# Sheet2_Power_Supply.net
KiCad netlist of a schematic drawn in Altium Designer
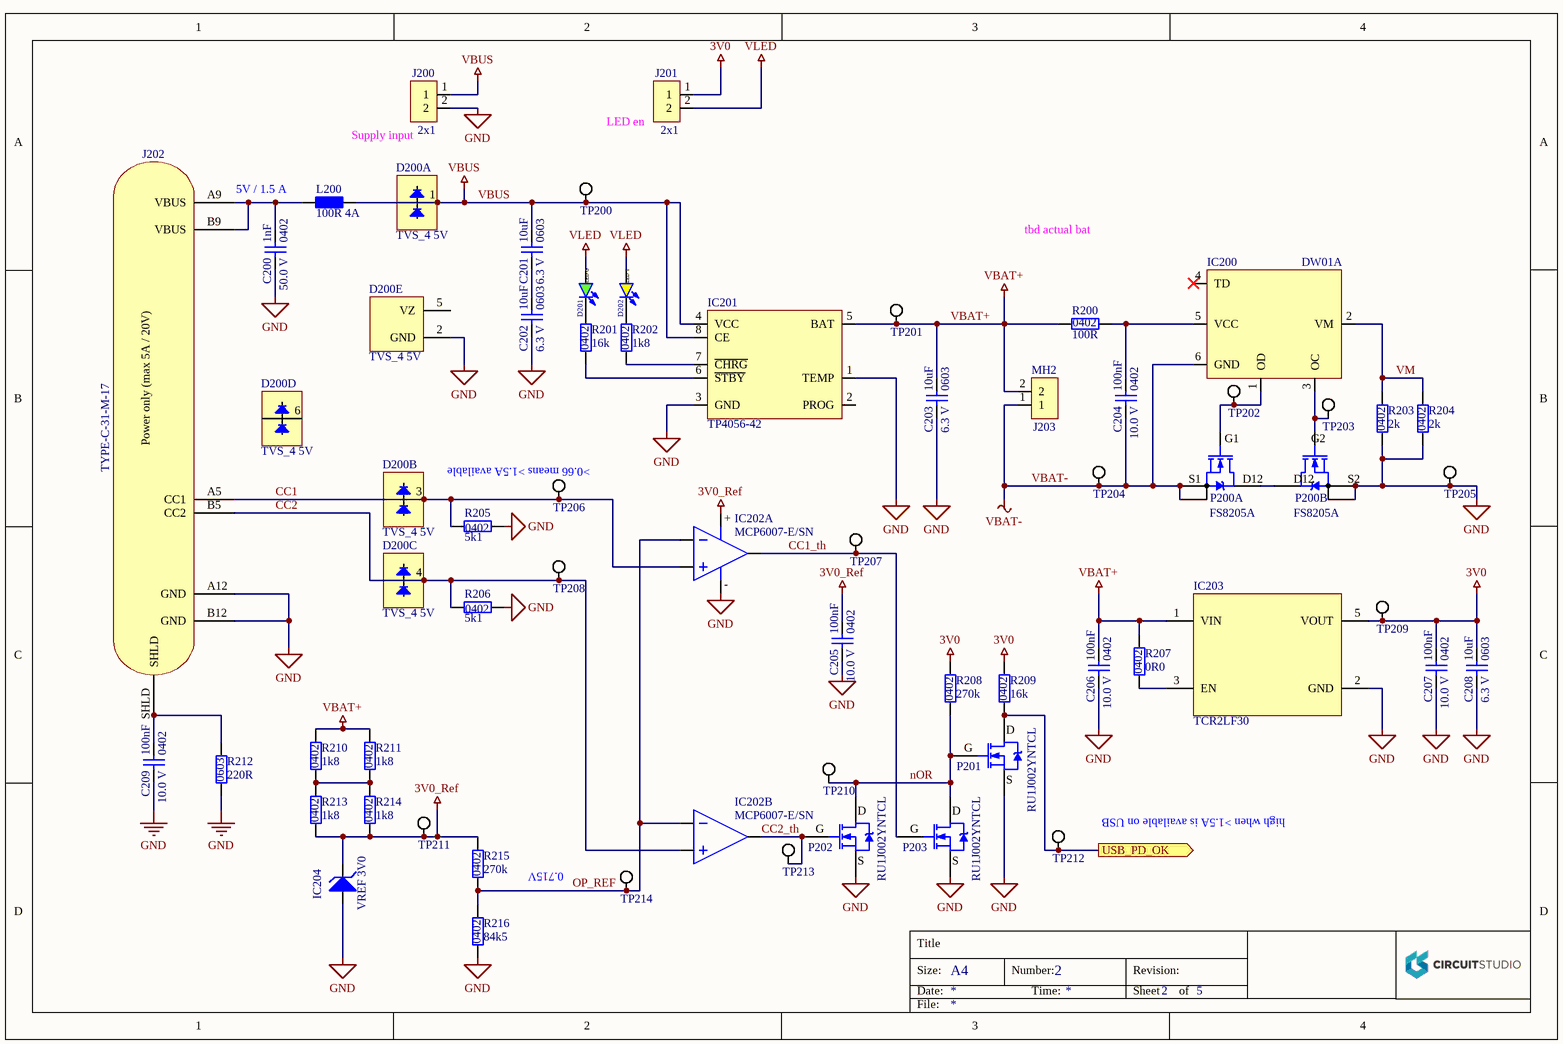
[diagram p0: Sheet2_Power_Supply.SchDoc]

(export (version "E")
  (design (tool "Eeschema 10.0.6"))
  (components
    (comp (ref "C200")
      (value "C 1nF 0402 50V")
      (footprint "0402")
      (description "CAP CER 1000PF 50V C0G/NP0 0402")
      (fields
        (field (name "MANUFACTURER") "Murata Electronics")
        (field (name "MANUFACTURER PART NUMBER") "GRM1555C1H102JA01J")
        (field (name "CAPACITANCE") "1nF")
        (field (name "VOLTAGE") "50.0 V")
      )
      (libsource (lib "CS_Part_Library") (part "CAP_1nF_50V_0402"))
    )
    (comp (ref "C201")
      (value "C 10uF 0603 6.3V")
      (footprint "0603")
      (description "CAP CER 10UF 6.3V X5R 0603")
      (fields
        (field (name "MANUFACTURER") "Taiyo Yuden")
        (field (name "MANUFACTURER PART NUMBER") "JMK107ABJ106MA-T")
        (field (name "CAPACITANCE") "10uF")
        (field (name "VOLTAGE") "6.3 V")
      )
      (libsource (lib "CS_Part_Library") (part "CAP_10uF_6V3_0603"))
    )
    (comp (ref "C202")
      (value "C 10uF 0603 6.3V")
      (footprint "0603")
      (description "CAP CER 10UF 6.3V X5R 0603")
      (fields
        (field (name "MANUFACTURER") "Taiyo Yuden")
        (field (name "MANUFACTURER PART NUMBER") "JMK107ABJ106MA-T")
        (field (name "CAPACITANCE") "10uF")
        (field (name "VOLTAGE") "6.3 V")
      )
      (libsource (lib "CS_Part_Library") (part "CAP_10uF_6V3_0603"))
    )
    (comp (ref "C203")
      (value "C 10uF 0603 6.3V")
      (footprint "0603")
      (description "CAP CER 10UF 6.3V X5R 0603")
      (fields
        (field (name "MANUFACTURER") "Taiyo Yuden")
        (field (name "MANUFACTURER PART NUMBER") "JMK107ABJ106MA-T")
        (field (name "CAPACITANCE") "10uF")
        (field (name "VOLTAGE") "6.3 V")
      )
      (libsource (lib "CS_Part_Library") (part "CAP_10uF_6V3_0603"))
    )
    (comp (ref "C204")
      (value "C 100nF 0402 10V")
      (footprint "0402")
      (description "CAP CER 0.1UF 10V X5R 0402")
      (fields
        (field (name "MANUFACTURER") "Samsung Electro-Mechanics")
        (field (name "MANUFACTURER PART NUMBER") "CL05A104MP5NNNC")
        (field (name "CAPACITANCE") "100nF")
        (field (name "VOLTAGE") "10.0 V")
      )
      (libsource (lib "CS_Part_Library") (part "CAP_100nF_10V_0402"))
    )
    (comp (ref "C205")
      (value "C 100nF 0402 10V")
      (footprint "0402")
      (description "CAP CER 0.1UF 10V X5R 0402")
      (fields
        (field (name "MANUFACTURER") "Samsung Electro-Mechanics")
        (field (name "MANUFACTURER PART NUMBER") "CL05A104MP5NNNC")
        (field (name "CAPACITANCE") "100nF")
        (field (name "VOLTAGE") "10.0 V")
      )
      (libsource (lib "CS_Part_Library") (part "CAP_100nF_10V_0402"))
    )
    (comp (ref "C206")
      (value "C 100nF 0402 10V")
      (footprint "0402")
      (description "CAP CER 0.1UF 10V X5R 0402")
      (fields
        (field (name "MANUFACTURER") "Samsung Electro-Mechanics")
        (field (name "MANUFACTURER PART NUMBER") "CL05A104MP5NNNC")
        (field (name "CAPACITANCE") "100nF")
        (field (name "VOLTAGE") "10.0 V")
      )
      (libsource (lib "CS_Part_Library") (part "CAP_100nF_10V_0402"))
    )
    (comp (ref "C207")
      (value "C 100nF 0402 10V")
      (footprint "0402")
      (description "CAP CER 0.1UF 10V X5R 0402")
      (fields
        (field (name "MANUFACTURER") "Samsung Electro-Mechanics")
        (field (name "MANUFACTURER PART NUMBER") "CL05A104MP5NNNC")
        (field (name "CAPACITANCE") "100nF")
        (field (name "VOLTAGE") "10.0 V")
      )
      (libsource (lib "CS_Part_Library") (part "CAP_100nF_10V_0402"))
    )
    (comp (ref "C208")
      (value "C 10uF 0603 6.3V")
      (footprint "0603")
      (description "CAP CER 10UF 6.3V X5R 0603")
      (fields
        (field (name "MANUFACTURER") "Taiyo Yuden")
        (field (name "MANUFACTURER PART NUMBER") "JMK107ABJ106MA-T")
        (field (name "CAPACITANCE") "10uF")
        (field (name "VOLTAGE") "6.3 V")
      )
      (libsource (lib "CS_Part_Library") (part "CAP_10uF_6V3_0603"))
    )
    (comp (ref "C209")
      (value "C 100nF 0402 10V")
      (footprint "0402")
      (description "CAP CER 0.1UF 10V X5R 0402")
      (fields
        (field (name "MANUFACTURER") "Samsung Electro-Mechanics")
        (field (name "MANUFACTURER PART NUMBER") "CL05A104MP5NNNC")
        (field (name "CAPACITANCE") "100nF")
        (field (name "VOLTAGE") "10.0 V")
      )
      (libsource (lib "CS_Part_Library") (part "CAP_100nF_10V_0402"))
    )
    (comp (ref "D200")
      (value "TVS_4 5V")
      (footprint "SOT-23-6")
      (description "TVS DIODE 5VWM 12.5VC SOT23-6")
      (fields
        (field (name "MANUFACTURER") "Comchip Technology")
        (field (name "MANUFACTURER PART NUMBER") "CPDT6-5V0UPC-HF")
      )
      (libsource (lib "CS_Part_Library") (part "D_TVS_U4_12V5"))
    )
    (comp (ref "D201")
      (value "LED G")
      (footprint "LED_0603")
      (description "LED GREEN DIFFUSED 0603 SMD")
      (fields
        (field (name "MANUFACTURER") "OSRAM Opto Semiconductors Inc.")
        (field (name "MANUFACTURER PART NUMBER") "LT Q39G-Q1OO-25-1")
      )
      (libsource (lib "CS_Part_Library") (part "D_LED_Green_0603"))
    )
    (comp (ref "D202")
      (value "LED Y")
      (footprint "LED_0603")
      (description "LED YELLOW DIFFUSED")
      (fields
        (field (name "MANUFACTURER") "Stanley Electric Co")
        (field (name "MANUFACTURER PART NUMBER") "FKY1111C-TR")
      )
      (libsource (lib "CS_Part_Library") (part "D_LED_Yellow_0603"))
    )
    (comp (ref "IC200")
      (value "DW01A")
      (footprint "SOT-23-6")
      (description "IC BATT MANAGEMENT SOT-23-6")
      (fields (field (name "MANUFACTURER") "PUOLOP"))
      (libsource (lib "CS_Part_Library") (part "IC_BAT_PROT_DW01A"))
    )
    (comp (ref "IC201")
      (value "TP4056-42")
      (footprint "SOIC-8-EP")
      (description "IC BATT CHG LI-ION 1CELL ESOP-8-EP")
      (fields
        (field (name "MANUFACTURER") "TOPPOWER(Nanjing Extension Microelectronics)")
        (field (name "MANUFACTURER PART NUMBER") "TP4056-42-ESOP8")
      )
      (libsource (lib "Symbols") (part "IC_BAT_CHGR_TP4056"))
    )
    (comp (ref "IC202")
      (value "MCP6007-E/SN")
      (footprint "SOIC-8")
      (description "DUAL, 1MHZ OP AMP, E TEMP")
      (fields (field (name "MANUFACTURER") "Microchip Technology"))
      (libsource (lib "CS_Part_Library") (part "IC_OpAmp_MCP6007-E/SN"))
    )
    (comp (ref "IC203")
      (value "TCR2LF30")
      (footprint "SOT-23-5")
      (description "IC REG LINEAR 3V 200MA SMV")
      (fields
        (field (name "MANUFACTURER") "Toshiba Semiconductor and Storage")
        (field (name "MANUFACTURER PART NUMBER") "TCR2LF30,LM(CT")
      )
      (libsource (lib "CS_Part_Library") (part "IC_Reg_TCR2LF30"))
    )
    (comp (ref "IC204")
      (value "VREF 3V0")
      (footprint "SOT-23-3")
      (description "IC VREF SHUNT 1% SOT23-3")
      (fields
        (field (name "MANUFACTURER") "Texas Instruments")
        (field (name "MANUFACTURER PART NUMBER") "LM4040DIM3X-3.0/NOPB")
      )
      (libsource (lib "Symbols") (part "IC_Ref_LM4040DIM3X-3.0"))
    )
    (comp (ref "J200")
      (value "2x1")
      (footprint "PH_1x2")
      (description "CONN HEADER VERT 2POS 2.54MM")
      (fields
        (field (name "MANUFACTURER") "Sullins Connector Solutions")
        (field (name "MANUFACTURER PART NUMBER") "PRPC002SAAN-RC")
      )
      (libsource (lib "CS_Part_Library") (part "J_MH2x1_2.54"))
    )
    (comp (ref "J201")
      (value "2x1")
      (footprint "PH_1x2")
      (description "CONN HEADER VERT 2POS 2.54MM")
      (fields
        (field (name "MANUFACTURER") "Sullins Connector Solutions")
        (field (name "MANUFACTURER PART NUMBER") "PRPC002SAAN-RC")
      )
      (libsource (lib "CS_Part_Library") (part "J_MH2x1_2.54"))
    )
    (comp (ref "J202")
      (value "TYPE-C-31-M-17")
      (footprint "Con_TYPE-C-31-M-17")
      (description "USB4 GEN3, TYPE C, TOP MOUNT")
      (fields (field (name "MANUFACTURER") "Korean Hroparts Elec"))
      (libsource (lib "CS_Part_Library") (part "J_USB-C_2"))
    )
    (comp (ref "J203")
      (value "MH2")
      (footprint "J_S2B-PH-K-S")
      (description "CONN HEADER R/A 2POS 2MM")
      (fields
        (field (name "MANUFACTURER") "JST Sales America Inc.")
        (field (name "MANUFACTURER PART NUMBER") "S2B-PH-KL(LF)(SN)")
      )
      (libsource (lib "CS_Part_Library") (part "J_S2B-PH-KL"))
    )
    (comp (ref "L200")
      (value "L Ferrite 100R 4A")
      (footprint "L_1206")
      (description "FIXED IND 100 4000MA 1206")
      (fields
        (field (name "MANUFACTURER") "Eaton - Electronics Division")
        (field (name "MANUFACTURER PART NUMBER") "MFBM1V3216-101-R")
        (field (name "INDUCTANCE") "100R 4A")
      )
      (libsource (lib "CS_Part_Library") (part "L_100R_4A"))
    )
    (comp (ref "P200")
      (value "P2 NMOS 20V 6A")
      (footprint "TSSOP-8_4.4mm")
      (description "MOSFET 2N_CH 20V 6A TSSOP-8")
      (fields
        (field (name "MANUFACTURER") "Fortune Semicon")
        (field (name "MANUFACTURER PART NUMBER") "FS8205A")
      )
      (libsource (lib "CS_Part_Library") (part "P_2NCH_20V_1W"))
    )
    (comp (ref "P201")
      (value "P_NCH_50V_150mW")
      (footprint "UMT3F")
      (description "MOSFET N-CH 50V 200MA UMT3F")
      (fields
        (field (name "MANUFACTURER") "Rohm Semiconductor")
        (field (name "MANUFACTURER PART NUMBER") "RU1J002YNTCL")
      )
      (libsource (lib "CS_Part_Library") (part "P_NCH_50V_150mW"))
    )
    (comp (ref "P202")
      (value "P_NCH_50V_150mW")
      (footprint "UMT3F")
      (description "MOSFET N-CH 50V 200MA UMT3F")
      (fields
        (field (name "MANUFACTURER") "Rohm Semiconductor")
        (field (name "MANUFACTURER PART NUMBER") "RU1J002YNTCL")
      )
      (libsource (lib "CS_Part_Library") (part "P_NCH_50V_150mW"))
    )
    (comp (ref "P203")
      (value "P_NCH_50V_150mW")
      (footprint "UMT3F")
      (description "MOSFET N-CH 50V 200MA UMT3F")
      (fields
        (field (name "MANUFACTURER") "Rohm Semiconductor")
        (field (name "MANUFACTURER PART NUMBER") "RU1J002YNTCL")
      )
      (libsource (lib "CS_Part_Library") (part "P_NCH_50V_150mW"))
    )
    (comp (ref "R200")
      (value "R 100R 0402")
      (footprint "0402")
      (description "RES 100 OHM 1% 1/16W 0402")
      (fields
        (field (name "MANUFACTURER") "Stackpole Electronics Inc")
        (field (name "MANUFACTURER PART NUMBER") "RMCF0402FT100R")
        (field (name "RESISTANCE") "100R")
      )
      (libsource (lib "CS_Part_Library") (part "R_100R_0402"))
    )
    (comp (ref "R201")
      (value "R 16k 0402")
      (footprint "0402")
      (description "RES 16K OHM 1% 1/16W 0402")
      (fields
        (field (name "MANUFACTURER") "Stackpole Electronics Inc")
        (field (name "MANUFACTURER PART NUMBER") "RMCF0402FT16K0")
        (field (name "RESISTANCE") "16k")
      )
      (libsource (lib "CS_Part_Library") (part "R_16k_0402"))
    )
    (comp (ref "R202")
      (value "R 1k8 0402")
      (footprint "0402")
      (description "RES 1.8K OHM 1% 1/16W 0402")
      (fields
        (field (name "MANUFACTURER") "Stackpole Electronics Inc")
        (field (name "MANUFACTURER PART NUMBER") "RMCF0402FT1K80")
        (field (name "RESISTANCE") "1k8")
      )
      (libsource (lib "CS_Part_Library") (part "R_1k8_0402"))
    )
    (comp (ref "R203")
      (value "R 2k 0402")
      (footprint "0402")
      (description "RES 2K OHM 1% 1/16W 0402")
      (fields
        (field (name "MANUFACTURER") "Stackpole Electronics Inc")
        (field (name "MANUFACTURER PART NUMBER") "RMCF0402FT2K00")
        (field (name "RESISTANCE") "2k")
      )
      (libsource (lib "CS_Part_Library") (part "R_2k_0402"))
    )
    (comp (ref "R204")
      (value "R 2k 0402")
      (footprint "0402")
      (description "RES 2K OHM 1% 1/16W 0402")
      (fields
        (field (name "MANUFACTURER") "Stackpole Electronics Inc")
        (field (name "MANUFACTURER PART NUMBER") "RMCF0402FT2K00")
        (field (name "RESISTANCE") "2k")
      )
      (libsource (lib "CS_Part_Library") (part "R_2k_0402"))
    )
    (comp (ref "R205")
      (value "R 5k1 0402")
      (footprint "0402")
      (description "RES 5.1K OHM 1% 1/16W 0402")
      (fields
        (field (name "MANUFACTURER") "Stackpole Electronics Inc")
        (field (name "MANUFACTURER PART NUMBER") "RMCF0402FT5K10")
        (field (name "RESISTANCE") "5k1")
      )
      (libsource (lib "CS_Part_Library") (part "R_5k1_0420"))
    )
    (comp (ref "R206")
      (value "R 5k1 0402")
      (footprint "0402")
      (description "RES 5.1K OHM 1% 1/16W 0402")
      (fields
        (field (name "MANUFACTURER") "Stackpole Electronics Inc")
        (field (name "MANUFACTURER PART NUMBER") "RMCF0402FT5K10")
        (field (name "RESISTANCE") "5k1")
      )
      (libsource (lib "CS_Part_Library") (part "R_5k1_0420"))
    )
    (comp (ref "R207")
      (value "R 0R0 0402")
      (footprint "0402")
      (description "RES 0 OHM JUMPER 1/16W 0402")
      (fields
        (field (name "MANUFACTURER") "Stackpole Electronics Inc")
        (field (name "MANUFACTURER PART NUMBER") "RMCF0402ZT0R00")
        (field (name "RESISTANCE") "0R0")
      )
      (libsource (lib "CS_Part_Library") (part "R_0R0_0402"))
    )
    (comp (ref "R208")
      (value "R 270k 0402")
      (footprint "0402")
      (description "RES 270K OHM 1% 1/16W 0402")
      (fields
        (field (name "MANUFACTURER") "YAGEO")
        (field (name "MANUFACTURER PART NUMBER") "RC0402FR-07270KL")
        (field (name "RESISTANCE") "270k")
      )
      (libsource (lib "CS_Part_Library") (part "R_270k_0402"))
    )
    (comp (ref "R209")
      (value "R 16k 0402")
      (footprint "0402")
      (description "RES 16K OHM 1% 1/16W 0402")
      (fields
        (field (name "MANUFACTURER") "Stackpole Electronics Inc")
        (field (name "MANUFACTURER PART NUMBER") "RMCF0402FT16K0")
        (field (name "RESISTANCE") "16k")
      )
      (libsource (lib "CS_Part_Library") (part "R_16k_0402"))
    )
    (comp (ref "R210")
      (value "R 1k8 0402")
      (footprint "0402")
      (description "RES 1.8K OHM 1% 1/16W 0402")
      (fields
        (field (name "MANUFACTURER") "Stackpole Electronics Inc")
        (field (name "MANUFACTURER PART NUMBER") "RMCF0402FT1K80")
        (field (name "RESISTANCE") "1k8")
      )
      (libsource (lib "CS_Part_Library") (part "R_1k8_0402"))
    )
    (comp (ref "R211")
      (value "R 1k8 0402")
      (footprint "0402")
      (description "RES 1.8K OHM 1% 1/16W 0402")
      (fields
        (field (name "MANUFACTURER") "Stackpole Electronics Inc")
        (field (name "MANUFACTURER PART NUMBER") "RMCF0402FT1K80")
        (field (name "RESISTANCE") "1k8")
      )
      (libsource (lib "CS_Part_Library") (part "R_1k8_0402"))
    )
    (comp (ref "R212")
      (value "R 220R 0603")
      (footprint "0603")
      (description "RES 220 OHM 1% 1/10W 0603")
      (fields
        (field (name "MANUFACTURER") "Stackpole Electronics Inc")
        (field (name "MANUFACTURER PART NUMBER") "RMCF0603FT220R")
        (field (name "RESISTANCE") "220R")
      )
      (libsource (lib "CS_Part_Library") (part "R_220R_0603"))
    )
    (comp (ref "R213")
      (value "R 1k8 0402")
      (footprint "0402")
      (description "RES 1.8K OHM 1% 1/16W 0402")
      (fields
        (field (name "MANUFACTURER") "Stackpole Electronics Inc")
        (field (name "MANUFACTURER PART NUMBER") "RMCF0402FT1K80")
        (field (name "RESISTANCE") "1k8")
      )
      (libsource (lib "CS_Part_Library") (part "R_1k8_0402"))
    )
    (comp (ref "R214")
      (value "R 1k8 0402")
      (footprint "0402")
      (description "RES 1.8K OHM 1% 1/16W 0402")
      (fields
        (field (name "MANUFACTURER") "Stackpole Electronics Inc")
        (field (name "MANUFACTURER PART NUMBER") "RMCF0402FT1K80")
        (field (name "RESISTANCE") "1k8")
      )
      (libsource (lib "CS_Part_Library") (part "R_1k8_0402"))
    )
    (comp (ref "R215")
      (value "R 270k 0402")
      (footprint "0402")
      (description "RES 270K OHM 1% 1/16W 0402")
      (fields
        (field (name "MANUFACTURER") "YAGEO")
        (field (name "MANUFACTURER PART NUMBER") "RC0402FR-07270KL")
        (field (name "RESISTANCE") "270k")
      )
      (libsource (lib "CS_Part_Library") (part "R_270k_0402"))
    )
    (comp (ref "R216")
      (value "R 84k5 0402")
      (footprint "0402")
      (description "RES SMD 84.5K OHM 1% 1/16W 0402")
      (fields
        (field (name "MANUFACTURER") "Vishay Dale")
        (field (name "MANUFACTURER PART NUMBER") "CRCW040284K5FKED")
        (field (name "RESISTANCE") "84k5")
      )
      (libsource (lib "CS_Part_Library") (part "R_84k5_0402"))
    )
    (comp (ref "TP200")
      (value "TP")
      (footprint "TP_1mm")
      (description "Test Point 1mm")
      (libsource (lib "CS_Part_Library") (part "TP_1mm"))
    )
    (comp (ref "TP201")
      (value "TP")
      (footprint "TP_1mm")
      (description "Test Point 1mm")
      (libsource (lib "CS_Part_Library") (part "TP_1mm"))
    )
    (comp (ref "TP202")
      (value "TP")
      (footprint "TP_1mm")
      (description "Test Point 1mm")
      (libsource (lib "CS_Part_Library") (part "TP_1mm"))
    )
    (comp (ref "TP203")
      (value "TP")
      (footprint "TP_1mm")
      (description "Test Point 1mm")
      (libsource (lib "CS_Part_Library") (part "TP_1mm"))
    )
    (comp (ref "TP204")
      (value "TP")
      (footprint "TP_1mm")
      (description "Test Point 1mm")
      (libsource (lib "CS_Part_Library") (part "TP_1mm"))
    )
    (comp (ref "TP205")
      (value "TP")
      (footprint "TP_1mm")
      (description "Test Point 1mm")
      (libsource (lib "CS_Part_Library") (part "TP_1mm"))
    )
    (comp (ref "TP206")
      (value "TP")
      (footprint "TP_1mm")
      (description "Test Point 1mm")
      (libsource (lib "CS_Part_Library") (part "TP_1mm"))
    )
    (comp (ref "TP207")
      (value "TP")
      (footprint "TP_1mm")
      (description "Test Point 1mm")
      (libsource (lib "CS_Part_Library") (part "TP_1mm"))
    )
    (comp (ref "TP208")
      (value "TP")
      (footprint "TP_1mm")
      (description "Test Point 1mm")
      (libsource (lib "CS_Part_Library") (part "TP_1mm"))
    )
    (comp (ref "TP209")
      (value "TP")
      (footprint "TP_1mm")
      (description "Test Point 1mm")
      (libsource (lib "CS_Part_Library") (part "TP_1mm"))
    )
    (comp (ref "TP210")
      (value "TP")
      (footprint "TP_1mm")
      (description "Test Point 1mm")
      (libsource (lib "CS_Part_Library") (part "TP_1mm"))
    )
    (comp (ref "TP211")
      (value "TP")
      (footprint "TP_1mm")
      (description "Test Point 1mm")
      (libsource (lib "CS_Part_Library") (part "TP_1mm"))
    )
    (comp (ref "TP212")
      (value "TP")
      (footprint "TP_1mm")
      (description "Test Point 1mm")
      (libsource (lib "CS_Part_Library") (part "TP_1mm"))
    )
    (comp (ref "TP213")
      (value "TP")
      (footprint "TP_1mm")
      (description "Test Point 1mm")
      (libsource (lib "CS_Part_Library") (part "TP_1mm"))
    )
    (comp (ref "TP214")
      (value "TP")
      (footprint "TP_1mm")
      (description "Test Point 1mm")
      (libsource (lib "CS_Part_Library") (part "TP_1mm"))
    )
  )
  (nets
    (net (code "1") (name "/CC1") (class "Default")
      (node (ref "D200") (pin "3") (pinfunction "3_3") (pintype "passive"))
      (node (ref "IC202") (pin "3") (pinfunction "INA+_3") (pintype "passive"))
      (node (ref "J202") (pin "A5") (pinfunction "CC1_A5") (pintype "passive"))
      (node (ref "R205") (pin "2") (pinfunction "2_2") (pintype "passive"))
      (node (ref "TP206") (pin "1") (pinfunction "TP_1") (pintype "passive"))
    )
    (net (code "2") (name "/CC1_th") (class "Default")
      (node (ref "IC202") (pin "1") (pinfunction "OUTA_1") (pintype "passive"))
      (node (ref "P203") (pin "1") (pinfunction "G_1") (pintype "passive"))
      (node (ref "TP207") (pin "1") (pinfunction "TP_1") (pintype "passive"))
    )
    (net (code "3") (name "/CC2") (class "Default")
      (node (ref "D200") (pin "4") (pinfunction "4_4") (pintype "passive"))
      (node (ref "IC202") (pin "5") (pinfunction "INB+_5") (pintype "passive"))
      (node (ref "J202") (pin "B5") (pinfunction "CC2_B5") (pintype "passive"))
      (node (ref "R206") (pin "2") (pinfunction "2_2") (pintype "passive"))
      (node (ref "TP208") (pin "1") (pinfunction "TP_1") (pintype "passive"))
    )
    (net (code "4") (name "/CC2_th") (class "Default")
      (node (ref "IC202") (pin "7") (pinfunction "OUTB_7") (pintype "passive"))
      (node (ref "P202") (pin "1") (pinfunction "G_1") (pintype "passive"))
      (node (ref "TP213") (pin "1") (pinfunction "TP_1") (pintype "passive"))
    )
    (net (code "5") (name "/OP_REF") (class "Default")
      (node (ref "IC202") (pin "2") (pinfunction "INA-_2") (pintype "passive"))
      (node (ref "IC202") (pin "6") (pinfunction "INB-_6") (pintype "passive"))
      (node (ref "R215") (pin "1") (pinfunction "1_1") (pintype "passive"))
      (node (ref "R216") (pin "2") (pinfunction "2_2") (pintype "passive"))
      (node (ref "TP214") (pin "1") (pinfunction "TP_1") (pintype "passive"))
    )
    (net (code "6") (name "/USB_PD_OK") (class "Default")
      (node (ref "P201") (pin "3") (pinfunction "D_3") (pintype "passive"))
      (node (ref "R209") (pin "1") (pinfunction "1_1") (pintype "passive"))
      (node (ref "TP212") (pin "1") (pinfunction "TP_1") (pintype "passive"))
    )
    (net (code "7") (name "/VM") (class "Default")
      (node (ref "IC200") (pin "2") (pinfunction "VM_2") (pintype "passive"))
      (node (ref "R203") (pin "2") (pinfunction "2_2") (pintype "passive"))
      (node (ref "R204") (pin "2") (pinfunction "2_2") (pintype "passive"))
    )
    (net (code "8") (name "/nOR") (class "Default")
      (node (ref "P201") (pin "1") (pinfunction "G_1") (pintype "passive"))
      (node (ref "P202") (pin "3") (pinfunction "D_3") (pintype "passive"))
      (node (ref "P203") (pin "3") (pinfunction "D_3") (pintype "passive"))
      (node (ref "R208") (pin "1") (pinfunction "1_1") (pintype "passive"))
      (node (ref "TP210") (pin "1") (pinfunction "TP_1") (pintype "passive"))
    )
    (net (code "9") (name "3V0") (class "Default")
      (node (ref "C207") (pin "2") (pinfunction "2_2") (pintype "passive"))
      (node (ref "C208") (pin "2") (pinfunction "2_2") (pintype "passive"))
      (node (ref "IC203") (pin "5") (pinfunction "VOUT_5") (pintype "passive"))
      (node (ref "J201") (pin "1") (pinfunction "1_1") (pintype "passive"))
      (node (ref "R208") (pin "2") (pinfunction "2_2") (pintype "passive"))
      (node (ref "R209") (pin "2") (pinfunction "2_2") (pintype "passive"))
      (node (ref "TP209") (pin "1") (pinfunction "TP_1") (pintype "passive"))
    )
    (net (code "10") (name "3V0_Ref") (class "Default")
      (node (ref "C205") (pin "2") (pinfunction "2_2") (pintype "passive"))
      (node (ref "IC202") (pin "8") (pinfunction "VDD_8") (pintype "passive"))
      (node (ref "IC204") (pin "1") (pinfunction "K_1") (pintype "passive"))
      (node (ref "R213") (pin "1") (pinfunction "1_1") (pintype "passive"))
      (node (ref "R214") (pin "1") (pinfunction "1_1") (pintype "passive"))
      (node (ref "R215") (pin "2") (pinfunction "2_2") (pintype "passive"))
      (node (ref "TP211") (pin "1") (pinfunction "TP_1") (pintype "passive"))
    )
    (net (code "11") (name "GND") (class "Default")
      (node (ref "C200") (pin "1") (pinfunction "1_1") (pintype "passive"))
      (node (ref "C202") (pin "1") (pinfunction "1_1") (pintype "passive"))
      (node (ref "C203") (pin "1") (pinfunction "1_1") (pintype "passive"))
      (node (ref "C205") (pin "1") (pinfunction "1_1") (pintype "passive"))
      (node (ref "C206") (pin "1") (pinfunction "1_1") (pintype "passive"))
      (node (ref "C207") (pin "1") (pinfunction "1_1") (pintype "passive"))
      (node (ref "C208") (pin "1") (pinfunction "1_1") (pintype "passive"))
      (node (ref "C209") (pin "1") (pinfunction "1_1") (pintype "passive"))
      (node (ref "D200") (pin "2") (pinfunction "GND_2") (pintype "passive"))
      (node (ref "IC201") (pin "1") (pinfunction "TEMP_1") (pintype "passive"))
      (node (ref "IC201") (pin "3") (pinfunction "GND_3") (pintype "passive"))
      (node (ref "IC202") (pin "4") (pinfunction "VSS_4") (pintype "passive"))
      (node (ref "IC203") (pin "2") (pinfunction "GND_2") (pintype "passive"))
      (node (ref "IC204") (pin "2") (pinfunction "A_2") (pintype "passive"))
      (node (ref "J200") (pin "2") (pinfunction "2_2") (pintype "passive"))
      (node (ref "J202") (pin "A12") (pinfunction "GND_A12") (pintype "passive"))
      (node (ref "J202") (pin "B12") (pinfunction "GND_B12") (pintype "passive"))
      (node (ref "P200") (pin "6") (pinfunction "S2_6") (pintype "passive"))
      (node (ref "P200") (pin "7") (pinfunction "S2_7") (pintype "passive"))
      (node (ref "P201") (pin "2") (pinfunction "S_2") (pintype "passive"))
      (node (ref "P202") (pin "2") (pinfunction "S_2") (pintype "passive"))
      (node (ref "P203") (pin "2") (pinfunction "S_2") (pintype "passive"))
      (node (ref "R203") (pin "1") (pinfunction "1_1") (pintype "passive"))
      (node (ref "R204") (pin "1") (pinfunction "1_1") (pintype "passive"))
      (node (ref "R205") (pin "1") (pinfunction "1_1") (pintype "passive"))
      (node (ref "R206") (pin "1") (pinfunction "1_1") (pintype "passive"))
      (node (ref "R212") (pin "1") (pinfunction "1_1") (pintype "passive"))
      (node (ref "R216") (pin "1") (pinfunction "1_1") (pintype "passive"))
      (node (ref "TP205") (pin "1") (pinfunction "TP_1") (pintype "passive"))
    )
    (net (code "12") (name "Net-(C200-Pad2)") (class "Default")
      (node (ref "C200") (pin "2") (pinfunction "2_2") (pintype "passive"))
      (node (ref "J202") (pin "A9") (pinfunction "VBUS_A9") (pintype "passive"))
      (node (ref "J202") (pin "B9") (pinfunction "VBUS_B9") (pintype "passive"))
      (node (ref "L200") (pin "1") (pinfunction "1_1") (pintype "passive"))
    )
    (net (code "13") (name "Net-(C201-Pad1)") (class "Default")
      (node (ref "C201") (pin "1") (pinfunction "1_1") (pintype "passive"))
      (node (ref "C202") (pin "2") (pinfunction "2_2") (pintype "passive"))
    )
    (net (code "14") (name "Net-(C209-Pad2)") (class "Default")
      (node (ref "C209") (pin "2") (pinfunction "2_2") (pintype "passive"))
      (node (ref "J202") (pin "SHLD") (pinfunction "SHLD_SHLD") (pintype "passive"))
      (node (ref "R212") (pin "2") (pinfunction "2_2") (pintype "passive"))
    )
    (net (code "15") (name "Net-(D201-PadK)") (class "Default")
      (node (ref "D201") (pin "K") (pinfunction "K_K") (pintype "passive"))
      (node (ref "R201") (pin "2") (pinfunction "2_2") (pintype "passive"))
    )
    (net (code "16") (name "Net-(D202-PadK)") (class "Default")
      (node (ref "D202") (pin "K") (pinfunction "K_K") (pintype "passive"))
      (node (ref "R202") (pin "2") (pinfunction "2_2") (pintype "passive"))
    )
    (net (code "17") (name "Net-(IC200-OC)") (class "Default")
      (node (ref "IC200") (pin "3") (pinfunction "OC_3") (pintype "passive"))
      (node (ref "P200") (pin "5") (pinfunction "G1_5") (pintype "passive"))
      (node (ref "TP203") (pin "1") (pinfunction "TP_1") (pintype "passive"))
    )
    (net (code "18") (name "Net-(IC200-OD)") (class "Default")
      (node (ref "IC200") (pin "1") (pinfunction "OD_1") (pintype "passive"))
      (node (ref "P200") (pin "4") (pinfunction "G1_4") (pintype "passive"))
      (node (ref "TP202") (pin "1") (pinfunction "TP_1") (pintype "passive"))
    )
    (net (code "19") (name "Net-(IC200-VCC)") (class "Default")
      (node (ref "C204") (pin "2") (pinfunction "2_2") (pintype "passive"))
      (node (ref "IC200") (pin "5") (pinfunction "VCC_5") (pintype "passive"))
      (node (ref "R200") (pin "2") (pinfunction "2_2") (pintype "passive"))
    )
    (net (code "20") (name "Net-(IC201-~{CHRG})") (class "Default")
      (node (ref "IC201") (pin "7") (pinfunction "~{CHRG}_7") (pintype "passive"))
      (node (ref "R202") (pin "1") (pinfunction "1_1") (pintype "passive"))
    )
    (net (code "21") (name "Net-(IC201-~{STBY})") (class "Default")
      (node (ref "IC201") (pin "6") (pinfunction "~{STBY}_6") (pintype "passive"))
      (node (ref "R201") (pin "1") (pinfunction "1_1") (pintype "passive"))
    )
    (net (code "22") (name "Net-(IC203-EN)") (class "Default")
      (node (ref "IC203") (pin "3") (pinfunction "EN_3") (pintype "passive"))
      (node (ref "R207") (pin "1") (pinfunction "1_1") (pintype "passive"))
    )
    (net (code "23") (name "Net-(P200A-D12)") (class "Default")
      (node (ref "P200") (pin "1") (pinfunction "D12_1") (pintype "passive"))
      (node (ref "P200") (pin "8") (pinfunction "D12_8") (pintype "passive"))
    )
    (net (code "24") (name "Net-(R210-Pad1)") (class "Default")
      (node (ref "R210") (pin "1") (pinfunction "1_1") (pintype "passive"))
      (node (ref "R211") (pin "1") (pinfunction "1_1") (pintype "passive"))
      (node (ref "R213") (pin "2") (pinfunction "2_2") (pintype "passive"))
      (node (ref "R214") (pin "2") (pinfunction "2_2") (pintype "passive"))
    )
    (net (code "25") (name "VBAT+") (class "Default")
      (node (ref "C203") (pin "2") (pinfunction "2_2") (pintype "passive"))
      (node (ref "C206") (pin "2") (pinfunction "2_2") (pintype "passive"))
      (node (ref "IC201") (pin "5") (pinfunction "BAT_5") (pintype "passive"))
      (node (ref "IC203") (pin "1") (pinfunction "VIN_1") (pintype "passive"))
      (node (ref "J203") (pin "2") (pinfunction "2_2") (pintype "passive"))
      (node (ref "R200") (pin "1") (pinfunction "1_1") (pintype "passive"))
      (node (ref "R207") (pin "2") (pinfunction "2_2") (pintype "passive"))
      (node (ref "R210") (pin "2") (pinfunction "2_2") (pintype "passive"))
      (node (ref "R211") (pin "2") (pinfunction "2_2") (pintype "passive"))
      (node (ref "TP201") (pin "1") (pinfunction "TP_1") (pintype "passive"))
    )
    (net (code "26") (name "VBAT-") (class "Default")
      (node (ref "C204") (pin "1") (pinfunction "1_1") (pintype "passive"))
      (node (ref "IC200") (pin "6") (pinfunction "GND_6") (pintype "passive"))
      (node (ref "J203") (pin "1") (pinfunction "1_1") (pintype "passive"))
      (node (ref "P200") (pin "2") (pinfunction "S1_2") (pintype "passive"))
      (node (ref "P200") (pin "3") (pinfunction "S1_3") (pintype "passive"))
      (node (ref "TP204") (pin "1") (pinfunction "TP_1") (pintype "passive"))
    )
    (net (code "27") (name "VBUS") (class "Default")
      (node (ref "C201") (pin "2") (pinfunction "2_2") (pintype "passive"))
      (node (ref "D200") (pin "1") (pinfunction "1_1") (pintype "passive"))
      (node (ref "IC201") (pin "4") (pinfunction "VCC_4") (pintype "passive"))
      (node (ref "IC201") (pin "8") (pinfunction "CE_8") (pintype "passive"))
      (node (ref "J200") (pin "1") (pinfunction "1_1") (pintype "passive"))
      (node (ref "L200") (pin "2") (pinfunction "2_2") (pintype "passive"))
      (node (ref "TP200") (pin "1") (pinfunction "TP_1") (pintype "passive"))
    )
    (net (code "28") (name "VLED") (class "Default")
      (node (ref "D201") (pin "A") (pinfunction "A_A") (pintype "passive"))
      (node (ref "D202") (pin "A") (pinfunction "A_A") (pintype "passive"))
      (node (ref "J201") (pin "2") (pinfunction "2_2") (pintype "passive"))
    )
    (net (code "29") (name "unconnected-(D200-Pad6)") (class "Default")
      (node (ref "D200") (pin "6") (pinfunction "6_6") (pintype "passive"))
    )
    (net (code "30") (name "unconnected-(D200E-VZ-Pad5)") (class "Default")
      (node (ref "D200") (pin "5") (pinfunction "VZ_5") (pintype "passive"))
    )
    (net (code "31") (name "unconnected-(IC200-TD-Pad4)") (class "Default")
      (node (ref "IC200") (pin "4") (pinfunction "TD_4") (pintype "passive+no_connect"))
    )
    (net (code "32") (name "unconnected-(IC201-PROG-Pad2)") (class "Default")
      (node (ref "IC201") (pin "2") (pinfunction "PROG_2") (pintype "passive"))
    )
  )
)
